# adc-rtc-shield.net
KiCad netlist of a schematic drawn in EAGLE
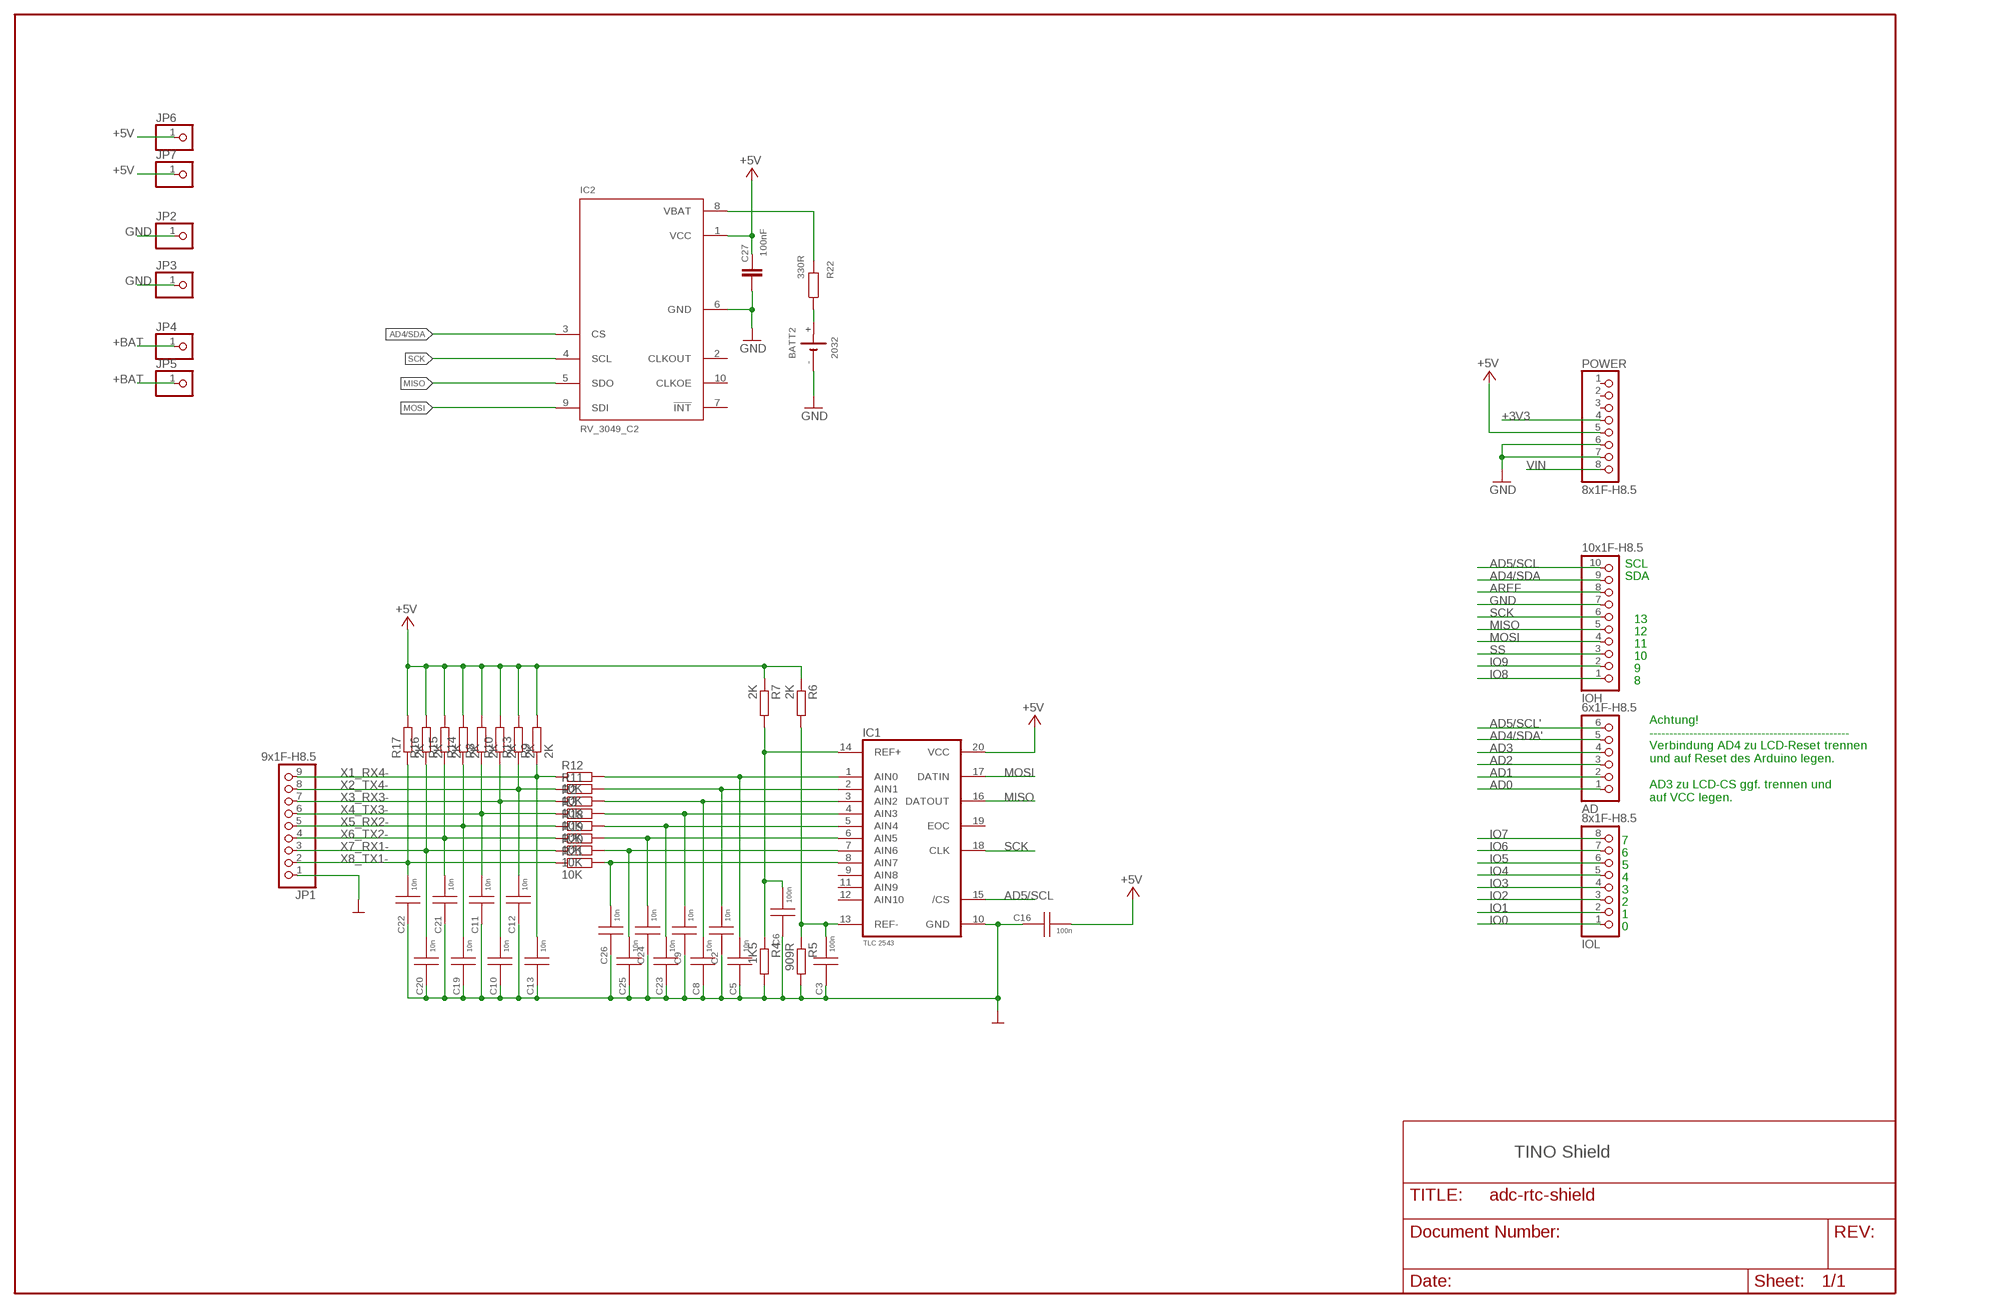
[diagram p0: schematic, sheet 1]

(export (version "E")
  (design (tool "Eeschema 10.0.6"))
  (components
    (comp (ref "AD")
      (value "6x1F-H8.5")
      (footprint "eagle-import:1X06")
      (libsource (lib "eagle-import") (part "PINHD-1X6"))
    )
    (comp (ref "BATT2")
      (value "2032")
      (footprint "eagle-import:2032_SMD")
      (libsource (lib "eagle-import") (part "CR2032_HOLDSMD"))
    )
    (comp (ref "C2")
      (value "10n")
      (footprint "eagle-import:0805-C")
      (libsource (lib "eagle-import") (part "C_KER"))
    )
    (comp (ref "C3")
      (value "100n")
      (footprint "eagle-import:0805-C")
      (libsource (lib "eagle-import") (part "C_KER"))
    )
    (comp (ref "C5")
      (value "10n")
      (footprint "eagle-import:0805-C")
      (libsource (lib "eagle-import") (part "C_KER"))
    )
    (comp (ref "C6")
      (value "100n")
      (footprint "eagle-import:0805-C")
      (libsource (lib "eagle-import") (part "C_KER"))
    )
    (comp (ref "C8")
      (value "10n")
      (footprint "eagle-import:0805-C")
      (libsource (lib "eagle-import") (part "C_KER"))
    )
    (comp (ref "C9")
      (value "10n")
      (footprint "eagle-import:0805-C")
      (libsource (lib "eagle-import") (part "C_KER"))
    )
    (comp (ref "C10")
      (value "10n")
      (footprint "eagle-import:0805-C")
      (libsource (lib "eagle-import") (part "C_KER"))
    )
    (comp (ref "C11")
      (value "10n")
      (footprint "eagle-import:0805-C")
      (libsource (lib "eagle-import") (part "C_KER"))
    )
    (comp (ref "C12")
      (value "10n")
      (footprint "eagle-import:0805-C")
      (libsource (lib "eagle-import") (part "C_KER"))
    )
    (comp (ref "C13")
      (value "10n")
      (footprint "eagle-import:0805-C")
      (libsource (lib "eagle-import") (part "C_KER"))
    )
    (comp (ref "C16")
      (value "100n")
      (footprint "eagle-import:0805-C")
      (libsource (lib "eagle-import") (part "C_KER"))
    )
    (comp (ref "C19")
      (value "10n")
      (footprint "eagle-import:0805-C")
      (libsource (lib "eagle-import") (part "C_KER"))
    )
    (comp (ref "C20")
      (value "10n")
      (footprint "eagle-import:0805-C")
      (libsource (lib "eagle-import") (part "C_KER"))
    )
    (comp (ref "C21")
      (value "10n")
      (footprint "eagle-import:0805-C")
      (libsource (lib "eagle-import") (part "C_KER"))
    )
    (comp (ref "C22")
      (value "10n")
      (footprint "eagle-import:0805-C")
      (libsource (lib "eagle-import") (part "C_KER"))
    )
    (comp (ref "C23")
      (value "10n")
      (footprint "eagle-import:0805-C")
      (libsource (lib "eagle-import") (part "C_KER"))
    )
    (comp (ref "C24")
      (value "10n")
      (footprint "eagle-import:0805-C")
      (libsource (lib "eagle-import") (part "C_KER"))
    )
    (comp (ref "C25")
      (value "10n")
      (footprint "eagle-import:0805-C")
      (libsource (lib "eagle-import") (part "C_KER"))
    )
    (comp (ref "C26")
      (value "10n")
      (footprint "eagle-import:0805-C")
      (libsource (lib "eagle-import") (part "C_KER"))
    )
    (comp (ref "C27")
      (value "100nF")
      (footprint "eagle-import:C0603")
      (libsource (lib "eagle-import") (part "C-EUC0603"))
    )
    (comp (ref "IC1")
      (value "TLC2543")
      (footprint "eagle-import:DIL_20")
      (libsource (lib "eagle-import") (part "TLC2543"))
    )
    (comp (ref "IC2")
      (value "RV_3049_C2")
      (footprint "eagle-import:5X3.2_10")
      (libsource (lib "eagle-import") (part "RV_3049_C2"))
    )
    (comp (ref "IOH")
      (value "10x1F-H8.5")
      (footprint "eagle-import:1X10")
      (libsource (lib "eagle-import") (part "PINHD-1X10_ARD"))
    )
    (comp (ref "IOL")
      (value "8x1F-H8.5")
      (footprint "eagle-import:1X08")
      (libsource (lib "eagle-import") (part "PINHD-1X8"))
    )
    (comp (ref "JP1")
      (value "9x1F-H8.5")
      (footprint "eagle-import:1X09_90")
      (libsource (lib "eagle-import") (part "PINHD-1X9/90"))
    )
    (comp (ref "JP2")
      (value "PINHD-1X1")
      (footprint "eagle-import:1X01")
      (libsource (lib "eagle-import") (part "PINHD-1X1"))
    )
    (comp (ref "JP3")
      (value "PINHD-1X1")
      (footprint "eagle-import:1X01")
      (libsource (lib "eagle-import") (part "PINHD-1X1"))
    )
    (comp (ref "JP4")
      (value "PINHD-1X1")
      (footprint "eagle-import:1X01")
      (libsource (lib "eagle-import") (part "PINHD-1X1"))
    )
    (comp (ref "JP5")
      (value "PINHD-1X1")
      (footprint "eagle-import:1X01")
      (libsource (lib "eagle-import") (part "PINHD-1X1"))
    )
    (comp (ref "JP6")
      (value "PINHD-1X1")
      (footprint "eagle-import:1X01")
      (libsource (lib "eagle-import") (part "PINHD-1X1"))
    )
    (comp (ref "JP7")
      (value "PINHD-1X1")
      (footprint "eagle-import:1X01")
      (libsource (lib "eagle-import") (part "PINHD-1X1"))
    )
    (comp (ref "POWER")
      (value "8x1F-H8.5")
      (footprint "eagle-import:1X08")
      (libsource (lib "eagle-import") (part "PINHD-1X8"))
    )
    (comp (ref "R2")
      (value "10K")
      (footprint "eagle-import:0207_12")
      (libsource (lib "eagle-import") (part "resistor_R-EU_0207/12"))
    )
    (comp (ref "R3")
      (value "10K")
      (footprint "eagle-import:0207_12")
      (libsource (lib "eagle-import") (part "resistor_R-EU_0207/12"))
    )
    (comp (ref "R4")
      (value "1K5")
      (footprint "eagle-import:0207_10")
      (libsource (lib "eagle-import") (part "resistor_R-EU_0207/10"))
    )
    (comp (ref "R5")
      (value "909R")
      (footprint "eagle-import:0207_10")
      (libsource (lib "eagle-import") (part "resistor_R-EU_0207/10"))
    )
    (comp (ref "R6")
      (value "2K")
      (footprint "eagle-import:0207_10")
      (libsource (lib "eagle-import") (part "resistor_R-EU_0207/10"))
    )
    (comp (ref "R7")
      (value "2K")
      (footprint "eagle-import:0207_12")
      (libsource (lib "eagle-import") (part "resistor_R-EU_0207/12"))
    )
    (comp (ref "R8")
      (value "2K")
      (footprint "eagle-import:0207_10")
      (libsource (lib "eagle-import") (part "resistor_R-EU_0207/10"))
    )
    (comp (ref "R9")
      (value "2K")
      (footprint "eagle-import:0207_10")
      (libsource (lib "eagle-import") (part "resistor_R-EU_0207/10"))
    )
    (comp (ref "R10")
      (value "2K")
      (footprint "eagle-import:0207_10")
      (libsource (lib "eagle-import") (part "resistor_R-EU_0207/10"))
    )
    (comp (ref "R11")
      (value "10K")
      (footprint "eagle-import:0207_12")
      (libsource (lib "eagle-import") (part "resistor_R-EU_0207/12"))
    )
    (comp (ref "R12")
      (value "10K")
      (footprint "eagle-import:0207_12")
      (libsource (lib "eagle-import") (part "resistor_R-EU_0207/12"))
    )
    (comp (ref "R13")
      (value "2K")
      (footprint "eagle-import:0207_10")
      (libsource (lib "eagle-import") (part "resistor_R-EU_0207/10"))
    )
    (comp (ref "R14")
      (value "2K")
      (footprint "eagle-import:0207_10")
      (libsource (lib "eagle-import") (part "resistor_R-EU_0207/10"))
    )
    (comp (ref "R15")
      (value "2K")
      (footprint "eagle-import:0207_10")
      (libsource (lib "eagle-import") (part "resistor_R-EU_0207/10"))
    )
    (comp (ref "R16")
      (value "2K")
      (footprint "eagle-import:0207_10")
      (libsource (lib "eagle-import") (part "resistor_R-EU_0207/10"))
    )
    (comp (ref "R17")
      (value "2K")
      (footprint "eagle-import:0207_10")
      (libsource (lib "eagle-import") (part "resistor_R-EU_0207/10"))
    )
    (comp (ref "R18")
      (value "10K")
      (footprint "eagle-import:0207_12")
      (libsource (lib "eagle-import") (part "resistor_R-EU_0207/12"))
    )
    (comp (ref "R19")
      (value "10K")
      (footprint "eagle-import:0207_12")
      (libsource (lib "eagle-import") (part "resistor_R-EU_0207/12"))
    )
    (comp (ref "R20")
      (value "10K")
      (footprint "eagle-import:0207_12")
      (libsource (lib "eagle-import") (part "resistor_R-EU_0207/12"))
    )
    (comp (ref "R21")
      (value "10K")
      (footprint "eagle-import:0207_12")
      (libsource (lib "eagle-import") (part "resistor_R-EU_0207/12"))
    )
    (comp (ref "R22")
      (value "330R")
      (footprint "eagle-import:0207_10")
      (libsource (lib "eagle-import") (part "R-EU_0207/10"))
    )
  )
  (nets
    (net (code "1") (name "+5V") (class "Default")
      (node (ref "C16") (pin "2") (pinfunction "2_2") (pintype "passive"))
      (node (ref "C27") (pin "1") (pinfunction "1_1") (pintype "passive"))
      (node (ref "IC1") (pin "20") (pinfunction "VCC_20") (pintype "power_in"))
      (node (ref "IC2") (pin "1") (pinfunction "VCC_1") (pintype "power_in"))
      (node (ref "JP6") (pin "1") (pinfunction "1_1") (pintype "passive"))
      (node (ref "JP7") (pin "1") (pinfunction "1_1") (pintype "passive"))
      (node (ref "POWER") (pin "5") (pinfunction "5_5") (pintype "passive"))
      (node (ref "R10") (pin "2") (pinfunction "2_2") (pintype "passive"))
      (node (ref "R13") (pin "2") (pinfunction "2_2") (pintype "passive"))
      (node (ref "R14") (pin "2") (pinfunction "2_2") (pintype "passive"))
      (node (ref "R15") (pin "2") (pinfunction "2_2") (pintype "passive"))
      (node (ref "R16") (pin "2") (pinfunction "2_2") (pintype "passive"))
      (node (ref "R17") (pin "2") (pinfunction "2_2") (pintype "passive"))
      (node (ref "R6") (pin "1") (pinfunction "1_1") (pintype "passive"))
      (node (ref "R7") (pin "1") (pinfunction "1_1") (pintype "passive"))
      (node (ref "R8") (pin "2") (pinfunction "2_2") (pintype "passive"))
      (node (ref "R9") (pin "2") (pinfunction "2_2") (pintype "passive"))
    )
    (net (code "2") (name "/+3V3") (class "Default")
      (node (ref "POWER") (pin "4") (pinfunction "4_4") (pintype "passive"))
    )
    (net (code "3") (name "/+BAT") (class "Default")
      (node (ref "BATT2") (pin "+") (pinfunction "+_+") (pintype "passive"))
      (node (ref "JP4") (pin "1") (pinfunction "1_1") (pintype "passive"))
      (node (ref "JP5") (pin "1") (pinfunction "1_1") (pintype "passive"))
      (node (ref "R22") (pin "1") (pinfunction "1_1") (pintype "passive"))
    )
    (net (code "4") (name "/AD0") (class "Default")
      (node (ref "AD") (pin "1") (pinfunction "1_1") (pintype "passive"))
    )
    (net (code "5") (name "/AD1") (class "Default")
      (node (ref "AD") (pin "2") (pinfunction "2_2") (pintype "passive"))
    )
    (net (code "6") (name "/AD2") (class "Default")
      (node (ref "AD") (pin "3") (pinfunction "3_3") (pintype "passive"))
    )
    (net (code "7") (name "/AD3") (class "Default")
      (node (ref "AD") (pin "4") (pinfunction "4_4") (pintype "passive"))
    )
    (net (code "8") (name "/AD4{slash}SDA'") (class "Default")
      (node (ref "AD") (pin "5") (pinfunction "5_5") (pintype "passive"))
    )
    (net (code "9") (name "/AD5{slash}SCL") (class "Default")
      (node (ref "IC1") (pin "15") (pinfunction "/CS_15") (pintype "input"))
      (node (ref "IOH") (pin "10") (pinfunction "10_10") (pintype "passive"))
    )
    (net (code "10") (name "/AD5{slash}SCL'") (class "Default")
      (node (ref "AD") (pin "6") (pinfunction "6_6") (pintype "passive"))
    )
    (net (code "11") (name "/AREF") (class "Default")
      (node (ref "IOH") (pin "8") (pinfunction "8_8") (pintype "passive"))
    )
    (net (code "12") (name "/IO0") (class "Default")
      (node (ref "IOL") (pin "1") (pinfunction "1_1") (pintype "passive"))
    )
    (net (code "13") (name "/IO1") (class "Default")
      (node (ref "IOL") (pin "2") (pinfunction "2_2") (pintype "passive"))
    )
    (net (code "14") (name "/IO2") (class "Default")
      (node (ref "IOL") (pin "3") (pinfunction "3_3") (pintype "passive"))
    )
    (net (code "15") (name "/IO3") (class "Default")
      (node (ref "IOL") (pin "4") (pinfunction "4_4") (pintype "passive"))
    )
    (net (code "16") (name "/IO4") (class "Default")
      (node (ref "IOL") (pin "5") (pinfunction "5_5") (pintype "passive"))
    )
    (net (code "17") (name "/IO5") (class "Default")
      (node (ref "IOL") (pin "6") (pinfunction "6_6") (pintype "passive"))
    )
    (net (code "18") (name "/IO6") (class "Default")
      (node (ref "IOL") (pin "7") (pinfunction "7_7") (pintype "passive"))
    )
    (net (code "19") (name "/IO7") (class "Default")
      (node (ref "IOL") (pin "8") (pinfunction "8_8") (pintype "passive"))
    )
    (net (code "20") (name "/IO8") (class "Default")
      (node (ref "IOH") (pin "1") (pinfunction "1_1") (pintype "passive"))
    )
    (net (code "21") (name "/IO9") (class "Default")
      (node (ref "IOH") (pin "2") (pinfunction "2_2") (pintype "passive"))
    )
    (net (code "22") (name "/SS") (class "Default")
      (node (ref "IOH") (pin "3") (pinfunction "3_3") (pintype "passive"))
    )
    (net (code "23") (name "/VIN") (class "Default")
      (node (ref "POWER") (pin "8") (pinfunction "8_8") (pintype "passive"))
    )
    (net (code "24") (name "/X1_RX4-") (class "Default")
      (node (ref "C13") (pin "2") (pinfunction "2_2") (pintype "passive"))
      (node (ref "JP1") (pin "9") (pinfunction "9_9") (pintype "passive"))
      (node (ref "R12") (pin "1") (pinfunction "1_1") (pintype "passive"))
      (node (ref "R9") (pin "1") (pinfunction "1_1") (pintype "passive"))
    )
    (net (code "25") (name "/X2_TX4-") (class "Default")
      (node (ref "C12") (pin "2") (pinfunction "2_2") (pintype "passive"))
      (node (ref "JP1") (pin "8") (pinfunction "8_8") (pintype "passive"))
      (node (ref "R11") (pin "1") (pinfunction "1_1") (pintype "passive"))
      (node (ref "R13") (pin "1") (pinfunction "1_1") (pintype "passive"))
    )
    (net (code "26") (name "/X3_RX3-") (class "Default")
      (node (ref "C10") (pin "2") (pinfunction "2_2") (pintype "passive"))
      (node (ref "JP1") (pin "7") (pinfunction "7_7") (pintype "passive"))
      (node (ref "R10") (pin "1") (pinfunction "1_1") (pintype "passive"))
      (node (ref "R2") (pin "1") (pinfunction "1_1") (pintype "passive"))
    )
    (net (code "27") (name "/X4_TX3-") (class "Default")
      (node (ref "C11") (pin "2") (pinfunction "2_2") (pintype "passive"))
      (node (ref "JP1") (pin "6") (pinfunction "6_6") (pintype "passive"))
      (node (ref "R3") (pin "1") (pinfunction "1_1") (pintype "passive"))
      (node (ref "R8") (pin "1") (pinfunction "1_1") (pintype "passive"))
    )
    (net (code "28") (name "/X5_RX2-") (class "Default")
      (node (ref "C19") (pin "2") (pinfunction "2_2") (pintype "passive"))
      (node (ref "JP1") (pin "5") (pinfunction "5_5") (pintype "passive"))
      (node (ref "R14") (pin "1") (pinfunction "1_1") (pintype "passive"))
      (node (ref "R18") (pin "1") (pinfunction "1_1") (pintype "passive"))
    )
    (net (code "29") (name "/X6_TX2-") (class "Default")
      (node (ref "C21") (pin "2") (pinfunction "2_2") (pintype "passive"))
      (node (ref "JP1") (pin "4") (pinfunction "4_4") (pintype "passive"))
      (node (ref "R15") (pin "1") (pinfunction "1_1") (pintype "passive"))
      (node (ref "R19") (pin "1") (pinfunction "1_1") (pintype "passive"))
    )
    (net (code "30") (name "/X7_RX1-") (class "Default")
      (node (ref "C20") (pin "2") (pinfunction "2_2") (pintype "passive"))
      (node (ref "JP1") (pin "3") (pinfunction "3_3") (pintype "passive"))
      (node (ref "R16") (pin "1") (pinfunction "1_1") (pintype "passive"))
      (node (ref "R20") (pin "1") (pinfunction "1_1") (pintype "passive"))
    )
    (net (code "31") (name "/X8_TX1-") (class "Default")
      (node (ref "C22") (pin "2") (pinfunction "2_2") (pintype "passive"))
      (node (ref "JP1") (pin "2") (pinfunction "2_2") (pintype "passive"))
      (node (ref "R17") (pin "1") (pinfunction "1_1") (pintype "passive"))
      (node (ref "R21") (pin "1") (pinfunction "1_1") (pintype "passive"))
    )
    (net (code "32") (name "AD4{slash}SDA") (class "Default")
      (node (ref "IC2") (pin "3") (pinfunction "CS_3") (pintype "input"))
      (node (ref "IOH") (pin "9") (pinfunction "9_9") (pintype "passive"))
    )
    (net (code "33") (name "GND") (class "Default")
      (node (ref "BATT2") (pin "-") (pinfunction "-_-") (pintype "passive"))
      (node (ref "C10") (pin "1") (pinfunction "1_1") (pintype "passive"))
      (node (ref "C11") (pin "1") (pinfunction "1_1") (pintype "passive"))
      (node (ref "C12") (pin "1") (pinfunction "1_1") (pintype "passive"))
      (node (ref "C13") (pin "1") (pinfunction "1_1") (pintype "passive"))
      (node (ref "C16") (pin "1") (pinfunction "1_1") (pintype "passive"))
      (node (ref "C19") (pin "1") (pinfunction "1_1") (pintype "passive"))
      (node (ref "C2") (pin "1") (pinfunction "1_1") (pintype "passive"))
      (node (ref "C20") (pin "1") (pinfunction "1_1") (pintype "passive"))
      (node (ref "C21") (pin "1") (pinfunction "1_1") (pintype "passive"))
      (node (ref "C22") (pin "1") (pinfunction "1_1") (pintype "passive"))
      (node (ref "C23") (pin "1") (pinfunction "1_1") (pintype "passive"))
      (node (ref "C24") (pin "1") (pinfunction "1_1") (pintype "passive"))
      (node (ref "C25") (pin "1") (pinfunction "1_1") (pintype "passive"))
      (node (ref "C26") (pin "1") (pinfunction "1_1") (pintype "passive"))
      (node (ref "C27") (pin "2") (pinfunction "2_2") (pintype "passive"))
      (node (ref "C3") (pin "1") (pinfunction "1_1") (pintype "passive"))
      (node (ref "C5") (pin "1") (pinfunction "1_1") (pintype "passive"))
      (node (ref "C6") (pin "1") (pinfunction "1_1") (pintype "passive"))
      (node (ref "C8") (pin "1") (pinfunction "1_1") (pintype "passive"))
      (node (ref "C9") (pin "1") (pinfunction "1_1") (pintype "passive"))
      (node (ref "IC1") (pin "10") (pinfunction "GND_10") (pintype "power_in"))
      (node (ref "IC2") (pin "6") (pinfunction "GND_6") (pintype "power_in"))
      (node (ref "IOH") (pin "7") (pinfunction "7_7") (pintype "passive"))
      (node (ref "JP1") (pin "1") (pinfunction "1_1") (pintype "passive"))
      (node (ref "JP2") (pin "1") (pinfunction "1_1") (pintype "passive"))
      (node (ref "JP3") (pin "1") (pinfunction "1_1") (pintype "passive"))
      (node (ref "POWER") (pin "6") (pinfunction "6_6") (pintype "passive"))
      (node (ref "POWER") (pin "7") (pinfunction "7_7") (pintype "passive"))
      (node (ref "R4") (pin "2") (pinfunction "2_2") (pintype "passive"))
      (node (ref "R5") (pin "2") (pinfunction "2_2") (pintype "passive"))
    )
    (net (code "34") (name "MISO") (class "Default")
      (node (ref "IC1") (pin "16") (pinfunction "DATOUT_16") (pintype "output"))
      (node (ref "IC2") (pin "5") (pinfunction "SDO_5") (pintype "output"))
      (node (ref "IOH") (pin "5") (pinfunction "5_5") (pintype "passive"))
    )
    (net (code "35") (name "MOSI") (class "Default")
      (node (ref "IC1") (pin "17") (pinfunction "DATIN_17") (pintype "input"))
      (node (ref "IC2") (pin "9") (pinfunction "SDI_9") (pintype "input"))
      (node (ref "IOH") (pin "4") (pinfunction "4_4") (pintype "passive"))
    )
    (net (code "36") (name "Net-(IC1-AIN0)") (class "Default")
      (node (ref "C5") (pin "2") (pinfunction "2_2") (pintype "passive"))
      (node (ref "IC1") (pin "1") (pinfunction "AIN0_1") (pintype "input"))
      (node (ref "R12") (pin "2") (pinfunction "2_2") (pintype "passive"))
    )
    (net (code "37") (name "Net-(IC1-AIN1)") (class "Default")
      (node (ref "C2") (pin "2") (pinfunction "2_2") (pintype "passive"))
      (node (ref "IC1") (pin "2") (pinfunction "AIN1_2") (pintype "input"))
      (node (ref "R11") (pin "2") (pinfunction "2_2") (pintype "passive"))
    )
    (net (code "38") (name "Net-(IC1-AIN2)") (class "Default")
      (node (ref "C8") (pin "2") (pinfunction "2_2") (pintype "passive"))
      (node (ref "IC1") (pin "3") (pinfunction "AIN2_3") (pintype "input"))
      (node (ref "R2") (pin "2") (pinfunction "2_2") (pintype "passive"))
    )
    (net (code "39") (name "Net-(IC1-AIN3)") (class "Default")
      (node (ref "C9") (pin "2") (pinfunction "2_2") (pintype "passive"))
      (node (ref "IC1") (pin "4") (pinfunction "AIN3_4") (pintype "input"))
      (node (ref "R3") (pin "2") (pinfunction "2_2") (pintype "passive"))
    )
    (net (code "40") (name "Net-(IC1-AIN4)") (class "Default")
      (node (ref "C23") (pin "2") (pinfunction "2_2") (pintype "passive"))
      (node (ref "IC1") (pin "5") (pinfunction "AIN4_5") (pintype "input"))
      (node (ref "R18") (pin "2") (pinfunction "2_2") (pintype "passive"))
    )
    (net (code "41") (name "Net-(IC1-AIN5)") (class "Default")
      (node (ref "C24") (pin "2") (pinfunction "2_2") (pintype "passive"))
      (node (ref "IC1") (pin "6") (pinfunction "AIN5_6") (pintype "input"))
      (node (ref "R19") (pin "2") (pinfunction "2_2") (pintype "passive"))
    )
    (net (code "42") (name "Net-(IC1-AIN6)") (class "Default")
      (node (ref "C25") (pin "2") (pinfunction "2_2") (pintype "passive"))
      (node (ref "IC1") (pin "7") (pinfunction "AIN6_7") (pintype "input"))
      (node (ref "R20") (pin "2") (pinfunction "2_2") (pintype "passive"))
    )
    (net (code "43") (name "Net-(IC1-AIN7)") (class "Default")
      (node (ref "C26") (pin "2") (pinfunction "2_2") (pintype "passive"))
      (node (ref "IC1") (pin "8") (pinfunction "AIN7_8") (pintype "input"))
      (node (ref "R21") (pin "2") (pinfunction "2_2") (pintype "passive"))
    )
    (net (code "44") (name "Net-(IC1-REF+)") (class "Default")
      (node (ref "C6") (pin "2") (pinfunction "2_2") (pintype "passive"))
      (node (ref "IC1") (pin "14") (pinfunction "REF+_14") (pintype "input"))
      (node (ref "R4") (pin "1") (pinfunction "1_1") (pintype "passive"))
      (node (ref "R7") (pin "2") (pinfunction "2_2") (pintype "passive"))
    )
    (net (code "45") (name "Net-(IC1-REF-)") (class "Default")
      (node (ref "C3") (pin "2") (pinfunction "2_2") (pintype "passive"))
      (node (ref "IC1") (pin "13") (pinfunction "REF-_13") (pintype "input"))
      (node (ref "R5") (pin "1") (pinfunction "1_1") (pintype "passive"))
      (node (ref "R6") (pin "2") (pinfunction "2_2") (pintype "passive"))
    )
    (net (code "46") (name "Net-(IC2-VBAT)") (class "Default")
      (node (ref "IC2") (pin "8") (pinfunction "VBAT_8") (pintype "power_in"))
      (node (ref "R22") (pin "2") (pinfunction "2_2") (pintype "passive"))
    )
    (net (code "47") (name "SCK") (class "Default")
      (node (ref "IC1") (pin "18") (pinfunction "CLK_18") (pintype "input"))
      (node (ref "IC2") (pin "4") (pinfunction "SCL_4") (pintype "input"))
      (node (ref "IOH") (pin "6") (pinfunction "6_6") (pintype "passive"))
    )
    (net (code "48") (name "unconnected-(IC1-AIN8-Pad9)") (class "Default")
      (node (ref "IC1") (pin "9") (pinfunction "AIN8_9") (pintype "input"))
    )
    (net (code "49") (name "unconnected-(IC1-AIN9-Pad11)") (class "Default")
      (node (ref "IC1") (pin "11") (pinfunction "AIN9_11") (pintype "input"))
    )
    (net (code "50") (name "unconnected-(IC1-AIN10-Pad12)") (class "Default")
      (node (ref "IC1") (pin "12") (pinfunction "AIN10_12") (pintype "input"))
    )
    (net (code "51") (name "unconnected-(IC1-EOC-Pad19)") (class "Default")
      (node (ref "IC1") (pin "19") (pinfunction "EOC_19") (pintype "output"))
    )
    (net (code "52") (name "unconnected-(IC2-CLKOE-Pad10)") (class "Default")
      (node (ref "IC2") (pin "10") (pinfunction "CLKOE_10") (pintype "input"))
    )
    (net (code "53") (name "unconnected-(IC2-CLKOUT-Pad2)") (class "Default")
      (node (ref "IC2") (pin "2") (pinfunction "CLKOUT_2") (pintype "output"))
    )
    (net (code "54") (name "unconnected-(IC2-~{INT}-Pad7)") (class "Default")
      (node (ref "IC2") (pin "7") (pinfunction "~{INT}_7") (pintype "open_collector"))
    )
    (net (code "55") (name "unconnected-(POWER-Pad1)") (class "Default")
      (node (ref "POWER") (pin "1") (pinfunction "1_1") (pintype "passive"))
    )
    (net (code "56") (name "unconnected-(POWER-Pad2)") (class "Default")
      (node (ref "POWER") (pin "2") (pinfunction "2_2") (pintype "passive"))
    )
    (net (code "57") (name "unconnected-(POWER-Pad3)") (class "Default")
      (node (ref "POWER") (pin "3") (pinfunction "3_3") (pintype "passive"))
    )
  )
)
